# FilterControl_Schematic.net
KiCad netlist of a schematic drawn in Altium Designer
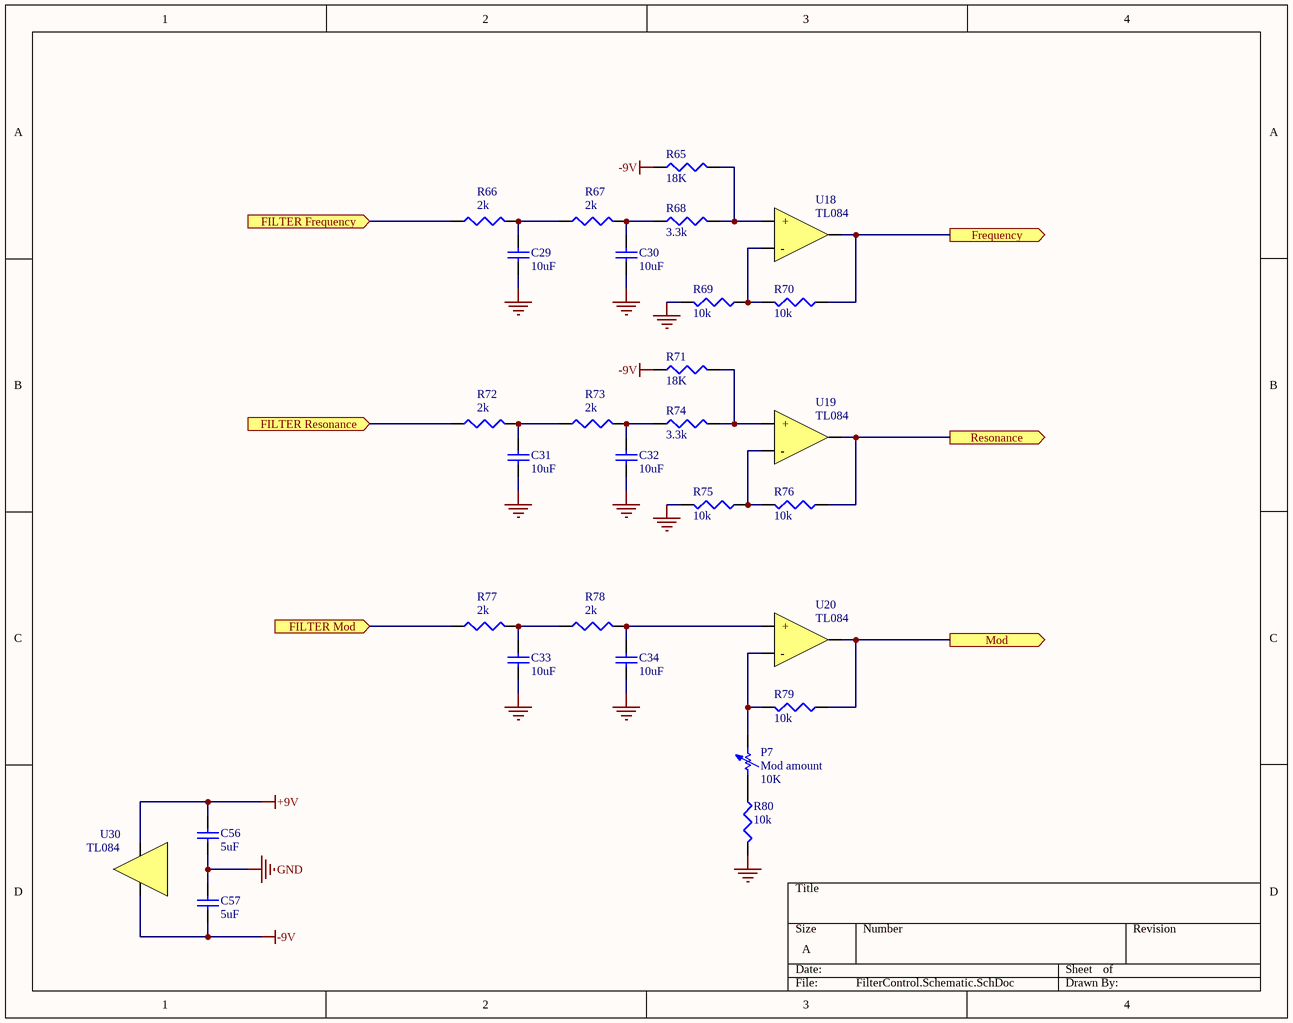
[diagram p0: FilterControl.Schematic.SchDoc]

(export (version "E")
  (design (tool "Eeschema 10.0.6"))
  (components
    (comp (ref "C29")
      (value "10uF")
      (footprint "CAPC1608N")
      (description "Capacitor (Semiconductor SIM Model)")
      (fields (field (name "PUBLISHER") "Altium Limited"))
      (libsource (lib "Miscellaneous Devices") (part "Cap Semi"))
    )
    (comp (ref "C30")
      (value "10uF")
      (footprint "CAPC1608N")
      (description "Capacitor (Semiconductor SIM Model)")
      (fields (field (name "PUBLISHER") "Altium Limited"))
      (libsource (lib "Miscellaneous Devices") (part "Cap Semi"))
    )
    (comp (ref "C31")
      (value "10uF")
      (footprint "CAPC1608N")
      (description "Capacitor (Semiconductor SIM Model)")
      (fields (field (name "PUBLISHER") "Altium Limited"))
      (libsource (lib "Miscellaneous Devices") (part "Cap Semi"))
    )
    (comp (ref "C32")
      (value "10uF")
      (footprint "CAPC1608N")
      (description "Capacitor (Semiconductor SIM Model)")
      (fields (field (name "PUBLISHER") "Altium Limited"))
      (libsource (lib "Miscellaneous Devices") (part "Cap Semi"))
    )
    (comp (ref "C33")
      (value "10uF")
      (footprint "CAPC1608N")
      (description "Capacitor (Semiconductor SIM Model)")
      (fields (field (name "PUBLISHER") "Altium Limited"))
      (libsource (lib "Miscellaneous Devices") (part "Cap Semi"))
    )
    (comp (ref "C34")
      (value "10uF")
      (footprint "CAPC1608N")
      (description "Capacitor (Semiconductor SIM Model)")
      (fields (field (name "PUBLISHER") "Altium Limited"))
      (libsource (lib "Miscellaneous Devices") (part "Cap Semi"))
    )
    (comp (ref "C56")
      (value "5uF")
      (footprint "CAPC1608N")
      (description "Capacitor (Semiconductor SIM Model)")
      (fields (field (name "PUBLISHER") "Altium Limited"))
      (libsource (lib "Miscellaneous Devices") (part "Cap Semi"))
    )
    (comp (ref "C57")
      (value "5uF")
      (footprint "CAPC1608N")
      (description "Capacitor (Semiconductor SIM Model)")
      (fields (field (name "PUBLISHER") "Altium Limited"))
      (libsource (lib "Miscellaneous Devices") (part "Cap Semi"))
    )
    (comp (ref "P7")
      (value "Mod amount")
      (footprint "CAPC1608N")
      (description "Variable Resistor")
      (fields (field (name "ALTIUM_VALUE") "10K") (field (name "PUBLISHER") "Altium Limited"))
      (libsource (lib "Miscellaneous Devices") (part "Res Adj1"))
    )
    (comp (ref "R65")
      (value "18K")
      (footprint "CAPC1608N")
      (description "Resistor")
      (fields (field (name "PUBLISHER") "Altium Limited"))
      (libsource (lib "Miscellaneous Devices") (part "Res3"))
    )
    (comp (ref "R66")
      (value "2k")
      (footprint "CAPC1608N")
      (description "Resistor")
      (fields (field (name "PUBLISHER") "Altium Limited"))
      (libsource (lib "Miscellaneous Devices") (part "Res3"))
    )
    (comp (ref "R67")
      (value "2k")
      (footprint "CAPC1608N")
      (description "Resistor")
      (fields (field (name "PUBLISHER") "Altium Limited"))
      (libsource (lib "Miscellaneous Devices") (part "Res3"))
    )
    (comp (ref "R68")
      (value "3.3k")
      (footprint "CAPC1608N")
      (description "Resistor")
      (fields (field (name "PUBLISHER") "Altium Limited"))
      (libsource (lib "Miscellaneous Devices") (part "Res3"))
    )
    (comp (ref "R69")
      (value "10k")
      (footprint "CAPC1608N")
      (description "Resistor")
      (fields (field (name "PUBLISHER") "Altium Limited"))
      (libsource (lib "Miscellaneous Devices") (part "Res3"))
    )
    (comp (ref "R70")
      (value "10k")
      (footprint "CAPC1608N")
      (description "Resistor")
      (fields (field (name "PUBLISHER") "Altium Limited"))
      (libsource (lib "Miscellaneous Devices") (part "Res3"))
    )
    (comp (ref "R71")
      (value "18K")
      (footprint "CAPC1608N")
      (description "Resistor")
      (fields (field (name "PUBLISHER") "Altium Limited"))
      (libsource (lib "Miscellaneous Devices") (part "Res3"))
    )
    (comp (ref "R72")
      (value "2k")
      (footprint "CAPC1608N")
      (description "Resistor")
      (fields (field (name "PUBLISHER") "Altium Limited"))
      (libsource (lib "Miscellaneous Devices") (part "Res3"))
    )
    (comp (ref "R73")
      (value "2k")
      (footprint "CAPC1608N")
      (description "Resistor")
      (fields (field (name "PUBLISHER") "Altium Limited"))
      (libsource (lib "Miscellaneous Devices") (part "Res3"))
    )
    (comp (ref "R74")
      (value "3.3k")
      (footprint "CAPC1608N")
      (description "Resistor")
      (fields (field (name "PUBLISHER") "Altium Limited"))
      (libsource (lib "Miscellaneous Devices") (part "Res3"))
    )
    (comp (ref "R75")
      (value "10k")
      (footprint "CAPC1608N")
      (description "Resistor")
      (fields (field (name "PUBLISHER") "Altium Limited"))
      (libsource (lib "Miscellaneous Devices") (part "Res3"))
    )
    (comp (ref "R76")
      (value "10k")
      (footprint "CAPC1608N")
      (description "Resistor")
      (fields (field (name "PUBLISHER") "Altium Limited"))
      (libsource (lib "Miscellaneous Devices") (part "Res3"))
    )
    (comp (ref "R77")
      (value "2k")
      (footprint "CAPC1608N")
      (description "Resistor")
      (fields (field (name "PUBLISHER") "Altium Limited"))
      (libsource (lib "Miscellaneous Devices") (part "Res3"))
    )
    (comp (ref "R78")
      (value "2k")
      (footprint "CAPC1608N")
      (description "Resistor")
      (fields (field (name "PUBLISHER") "Altium Limited"))
      (libsource (lib "Miscellaneous Devices") (part "Res3"))
    )
    (comp (ref "R79")
      (value "10k")
      (footprint "CAPC1608N")
      (description "Resistor")
      (fields (field (name "PUBLISHER") "Altium Limited"))
      (libsource (lib "Miscellaneous Devices") (part "Res3"))
    )
    (comp (ref "R80")
      (value "10k")
      (footprint "CAPC1608N")
      (description "Resistor")
      (fields (field (name "PUBLISHER") "Altium Limited"))
      (libsource (lib "Miscellaneous Devices") (part "Res3"))
    )
    (comp (ref "U18")
      (value "TL084")
      (footprint "TL084_3PADS")
      (libsource (lib "SynthyTwo.Components") (part "TL084"))
    )
    (comp (ref "U19")
      (value "TL084")
      (footprint "TL084_3PADS")
      (libsource (lib "SynthyTwo.Components") (part "TL084"))
    )
    (comp (ref "U20")
      (value "TL084")
      (footprint "TL084_3PADS")
      (libsource (lib "SynthyTwo.Components") (part "TL084"))
    )
    (comp (ref "U30")
      (value "TL084")
      (footprint "TL084_ALIM")
      (libsource (lib "SynthyTwo.Components") (part "TL_CLEAN"))
    )
  )
  (nets
    (net (code "1") (name "+9V") (class "Default")
      (node (ref "C56") (pin "1") (pinfunction "1_1") (pintype "passive"))
      (node (ref "U30") (pin "2") (pinfunction "VCC-_2") (pintype "passive"))
    )
    (net (code "2") (name "-9V") (class "Default")
      (node (ref "C57") (pin "2") (pinfunction "2_2") (pintype "passive"))
      (node (ref "R65") (pin "1") (pinfunction "1_1") (pintype "passive"))
      (node (ref "R71") (pin "1") (pinfunction "1_1") (pintype "passive"))
      (node (ref "U30") (pin "1") (pinfunction "VCC+_1") (pintype "passive"))
    )
    (net (code "3") (name "/FILTER Frequency") (class "Default")
      (node (ref "R66") (pin "1") (pinfunction "1_1") (pintype "passive"))
    )
    (net (code "4") (name "/FILTER Mod") (class "Default")
      (node (ref "R77") (pin "1") (pinfunction "1_1") (pintype "passive"))
    )
    (net (code "5") (name "/FILTER Resonance") (class "Default")
      (node (ref "R72") (pin "1") (pinfunction "1_1") (pintype "passive"))
    )
    (net (code "6") (name "/Frequency") (class "Default")
      (node (ref "R70") (pin "1") (pinfunction "1_1") (pintype "passive"))
      (node (ref "U18") (pin "1") (pinfunction "OUT_1") (pintype "passive"))
    )
    (net (code "7") (name "/Mod") (class "Default")
      (node (ref "R79") (pin "1") (pinfunction "1_1") (pintype "passive"))
      (node (ref "U20") (pin "1") (pinfunction "OUT_1") (pintype "passive"))
    )
    (net (code "8") (name "/Resonance") (class "Default")
      (node (ref "R76") (pin "1") (pinfunction "1_1") (pintype "passive"))
      (node (ref "U19") (pin "1") (pinfunction "OUT_1") (pintype "passive"))
    )
    (net (code "9") (name "GND") (class "Default")
      (node (ref "C29") (pin "1") (pinfunction "1_1") (pintype "passive"))
      (node (ref "C30") (pin "1") (pinfunction "1_1") (pintype "passive"))
      (node (ref "C31") (pin "1") (pinfunction "1_1") (pintype "passive"))
      (node (ref "C32") (pin "1") (pinfunction "1_1") (pintype "passive"))
      (node (ref "C33") (pin "1") (pinfunction "1_1") (pintype "passive"))
      (node (ref "C34") (pin "1") (pinfunction "1_1") (pintype "passive"))
      (node (ref "C56") (pin "2") (pinfunction "2_2") (pintype "passive"))
      (node (ref "C57") (pin "1") (pinfunction "1_1") (pintype "passive"))
      (node (ref "R69") (pin "2") (pinfunction "2_2") (pintype "passive"))
      (node (ref "R75") (pin "2") (pinfunction "2_2") (pintype "passive"))
      (node (ref "R80") (pin "2") (pinfunction "2_2") (pintype "passive"))
    )
    (net (code "10") (name "Net-(C29-Pad2)") (class "Default")
      (node (ref "C29") (pin "2") (pinfunction "2_2") (pintype "passive"))
      (node (ref "R66") (pin "2") (pinfunction "2_2") (pintype "passive"))
      (node (ref "R67") (pin "1") (pinfunction "1_1") (pintype "passive"))
    )
    (net (code "11") (name "Net-(C30-Pad2)") (class "Default")
      (node (ref "C30") (pin "2") (pinfunction "2_2") (pintype "passive"))
      (node (ref "R67") (pin "2") (pinfunction "2_2") (pintype "passive"))
      (node (ref "R68") (pin "1") (pinfunction "1_1") (pintype "passive"))
    )
    (net (code "12") (name "Net-(C31-Pad2)") (class "Default")
      (node (ref "C31") (pin "2") (pinfunction "2_2") (pintype "passive"))
      (node (ref "R72") (pin "2") (pinfunction "2_2") (pintype "passive"))
      (node (ref "R73") (pin "1") (pinfunction "1_1") (pintype "passive"))
    )
    (net (code "13") (name "Net-(C32-Pad2)") (class "Default")
      (node (ref "C32") (pin "2") (pinfunction "2_2") (pintype "passive"))
      (node (ref "R73") (pin "2") (pinfunction "2_2") (pintype "passive"))
      (node (ref "R74") (pin "1") (pinfunction "1_1") (pintype "passive"))
    )
    (net (code "14") (name "Net-(C33-Pad2)") (class "Default")
      (node (ref "C33") (pin "2") (pinfunction "2_2") (pintype "passive"))
      (node (ref "R77") (pin "2") (pinfunction "2_2") (pintype "passive"))
      (node (ref "R78") (pin "1") (pinfunction "1_1") (pintype "passive"))
    )
    (net (code "15") (name "Net-(P7-Pad1)") (class "Default")
      (node (ref "P7") (pin "1") (pinfunction "1_1") (pintype "passive"))
      (node (ref "R80") (pin "1") (pinfunction "1_1") (pintype "passive"))
    )
    (net (code "16") (name "Net-(U18-+)") (class "Default")
      (node (ref "R65") (pin "2") (pinfunction "2_2") (pintype "passive"))
      (node (ref "R68") (pin "2") (pinfunction "2_2") (pintype "passive"))
      (node (ref "U18") (pin "3") (pinfunction "+_3") (pintype "passive"))
    )
    (net (code "17") (name "Net-(U18--)") (class "Default")
      (node (ref "R69") (pin "1") (pinfunction "1_1") (pintype "passive"))
      (node (ref "R70") (pin "2") (pinfunction "2_2") (pintype "passive"))
      (node (ref "U18") (pin "2") (pinfunction "-_2") (pintype "passive"))
    )
    (net (code "18") (name "Net-(U19-+)") (class "Default")
      (node (ref "R71") (pin "2") (pinfunction "2_2") (pintype "passive"))
      (node (ref "R74") (pin "2") (pinfunction "2_2") (pintype "passive"))
      (node (ref "U19") (pin "3") (pinfunction "+_3") (pintype "passive"))
    )
    (net (code "19") (name "Net-(U19--)") (class "Default")
      (node (ref "R75") (pin "1") (pinfunction "1_1") (pintype "passive"))
      (node (ref "R76") (pin "2") (pinfunction "2_2") (pintype "passive"))
      (node (ref "U19") (pin "2") (pinfunction "-_2") (pintype "passive"))
    )
    (net (code "20") (name "Net-(U20-+)") (class "Default")
      (node (ref "C34") (pin "2") (pinfunction "2_2") (pintype "passive"))
      (node (ref "R78") (pin "2") (pinfunction "2_2") (pintype "passive"))
      (node (ref "U20") (pin "3") (pinfunction "+_3") (pintype "passive"))
    )
    (net (code "21") (name "Net-(U20--)") (class "Default")
      (node (ref "P7") (pin "2") (pinfunction "2_2") (pintype "passive"))
      (node (ref "R79") (pin "2") (pinfunction "2_2") (pintype "passive"))
      (node (ref "U20") (pin "2") (pinfunction "-_2") (pintype "passive"))
    )
  )
)
